# main.net
KiCad netlist of a schematic drawn in EAGLE
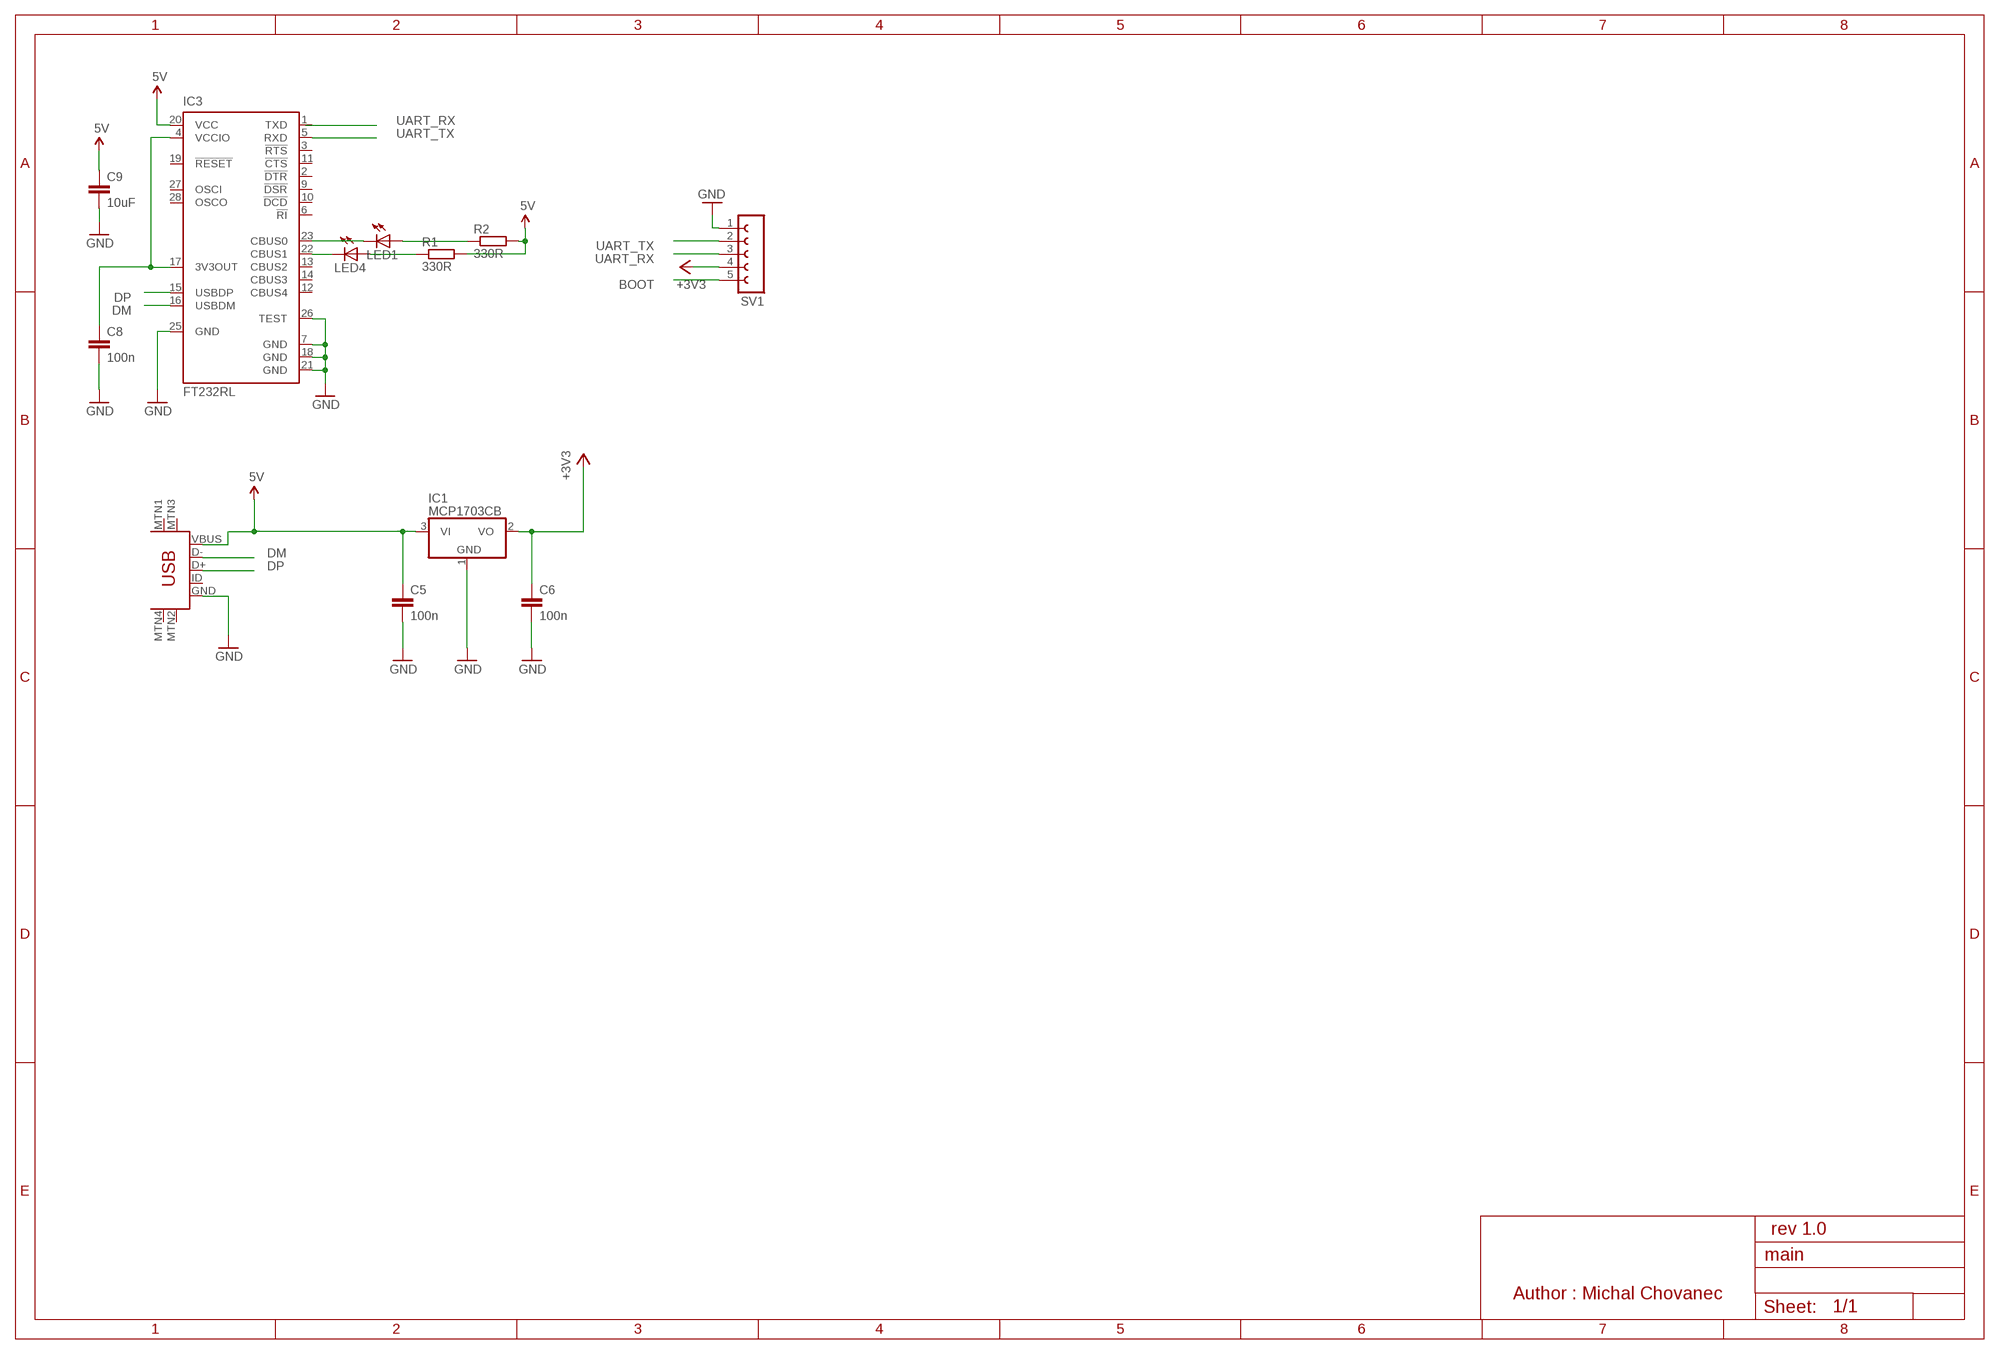
[diagram p0: schematic, sheet 1]

(export (version "E")
  (design (tool "Eeschema 10.0.6"))
  (components
    (comp (ref "C5")
      (value "100n")
      (footprint "eagle-import:C0805")
      (libsource (lib "eagle-import") (part "C-EUC0805"))
    )
    (comp (ref "C6")
      (value "100n")
      (footprint "eagle-import:C0805")
      (libsource (lib "eagle-import") (part "C-EUC0805"))
    )
    (comp (ref "C8")
      (value "100n")
      (footprint "eagle-import:C0805")
      (libsource (lib "eagle-import") (part "C-EUC0805"))
    )
    (comp (ref "C9")
      (value "10uF")
      (footprint "eagle-import:C0805")
      (libsource (lib "eagle-import") (part "C-EUC0805"))
    )
    (comp (ref "IC1")
      (value "MCP1703CB")
      (footprint "eagle-import:SOT23")
      (libsource (lib "eagle-import") (part "MCP1703CB"))
    )
    (comp (ref "IC3")
      (value "FT232RL")
      (footprint "eagle-import:SSOP28")
      (libsource (lib "eagle-import") (part "FT232RL"))
    )
    (comp (ref "LED1")
      (value "LEDCHIPLED_1206")
      (footprint "eagle-import:CHIPLED_1206")
      (libsource (lib "eagle-import") (part "LEDCHIPLED_1206"))
    )
    (comp (ref "LED4")
      (value "LEDCHIPLED_1206")
      (footprint "eagle-import:CHIPLED_1206")
      (libsource (lib "eagle-import") (part "LEDCHIPLED_1206"))
    )
    (comp (ref "R1")
      (value "330R")
      (footprint "eagle-import:M0805")
      (libsource (lib "eagle-import") (part "R-EU_M0805"))
    )
    (comp (ref "R2")
      (value "330R")
      (footprint "eagle-import:M0805")
      (libsource (lib "eagle-import") (part "R-EU_M0805"))
    )
    (comp (ref "SV1")
      (value "FE05-1")
      (footprint "eagle-import:FE05-1")
      (libsource (lib "eagle-import") (part "FE05-1"))
    )
    (comp (ref "U$1")
      (value "USB-MINIB-5PIN")
      (footprint "eagle-import:USB-MINIB")
      (libsource (lib "eagle-import") (part "USB-MINIB-5PIN"))
    )
  )
  (nets
    (net (code "1") (name "+3V3") (class "Default")
      (node (ref "C6") (pin "1") (pinfunction "1_1") (pintype "passive"))
      (node (ref "IC1") (pin "2") (pinfunction "VO_2") (pintype "passive"))
      (node (ref "SV1") (pin "4") (pinfunction "4_4") (pintype "passive"))
    )
    (net (code "2") (name "/BOOT") (class "Default")
      (node (ref "SV1") (pin "5") (pinfunction "5_5") (pintype "passive"))
    )
    (net (code "3") (name "/DM") (class "Default")
      (node (ref "IC3") (pin "16") (pinfunction "USBDM_16") (pintype "bidirectional"))
      (node (ref "U$1") (pin "D-") (pinfunction "D-_D-") (pintype "bidirectional"))
    )
    (net (code "4") (name "/DP") (class "Default")
      (node (ref "IC3") (pin "15") (pinfunction "USBDP_15") (pintype "bidirectional"))
      (node (ref "U$1") (pin "D+") (pinfunction "D+_D+") (pintype "bidirectional"))
    )
    (net (code "5") (name "/UART_RX") (class "Default")
      (node (ref "SV1") (pin "3") (pinfunction "3_3") (pintype "passive"))
    )
    (net (code "6") (name "/UART_TX") (class "Default")
      (node (ref "IC3") (pin "5") (pinfunction "RXD_5") (pintype "input"))
      (node (ref "SV1") (pin "2") (pinfunction "2_2") (pintype "passive"))
    )
    (net (code "7") (name "5V") (class "Default")
      (node (ref "C5") (pin "1") (pinfunction "1_1") (pintype "passive"))
      (node (ref "C9") (pin "1") (pinfunction "1_1") (pintype "passive"))
      (node (ref "IC1") (pin "3") (pinfunction "VI_3") (pintype "input"))
      (node (ref "IC3") (pin "20") (pinfunction "VCC_20") (pintype "power_in"))
      (node (ref "R1") (pin "2") (pinfunction "2_2") (pintype "passive"))
      (node (ref "R2") (pin "2") (pinfunction "2_2") (pintype "passive"))
      (node (ref "U$1") (pin "VBUS") (pinfunction "VBUS_VBUS") (pintype "bidirectional"))
    )
    (net (code "8") (name "GND") (class "Default")
      (node (ref "C5") (pin "2") (pinfunction "2_2") (pintype "passive"))
      (node (ref "C6") (pin "2") (pinfunction "2_2") (pintype "passive"))
      (node (ref "C8") (pin "2") (pinfunction "2_2") (pintype "passive"))
      (node (ref "C9") (pin "2") (pinfunction "2_2") (pintype "passive"))
      (node (ref "IC1") (pin "1") (pinfunction "GND_1") (pintype "passive"))
      (node (ref "IC3") (pin "18") (pinfunction "GND_18") (pintype "power_in"))
      (node (ref "IC3") (pin "21") (pinfunction "GND_21") (pintype "power_in"))
      (node (ref "IC3") (pin "25") (pinfunction "GND_25") (pintype "power_in"))
      (node (ref "IC3") (pin "26") (pinfunction "TEST_26") (pintype "input"))
      (node (ref "IC3") (pin "7") (pinfunction "GND_7") (pintype "power_in"))
      (node (ref "SV1") (pin "1") (pinfunction "1_1") (pintype "passive"))
      (node (ref "U$1") (pin "GND") (pinfunction "GND_GND") (pintype "bidirectional"))
    )
    (net (code "9") (name "Net-(IC3-3V3OUT)") (class "Default")
      (node (ref "C8") (pin "1") (pinfunction "1_1") (pintype "passive"))
      (node (ref "IC3") (pin "17") (pinfunction "3V3OUT_17") (pintype "output"))
      (node (ref "IC3") (pin "4") (pinfunction "VCCIO_4") (pintype "power_in"))
    )
    (net (code "10") (name "Net-(IC3-CBUS0)") (class "Default")
      (node (ref "IC3") (pin "23") (pinfunction "CBUS0_23") (pintype "bidirectional"))
      (node (ref "LED1") (pin "C") (pinfunction "C_C") (pintype "passive"))
    )
    (net (code "11") (name "Net-(IC3-CBUS1)") (class "Default")
      (node (ref "IC3") (pin "22") (pinfunction "CBUS1_22") (pintype "bidirectional"))
      (node (ref "LED4") (pin "C") (pinfunction "C_C") (pintype "passive"))
    )
    (net (code "12") (name "Net-(LED1-PadA)") (class "Default")
      (node (ref "LED1") (pin "A") (pinfunction "A_A") (pintype "passive"))
      (node (ref "R2") (pin "1") (pinfunction "1_1") (pintype "passive"))
    )
    (net (code "13") (name "Net-(LED4-PadA)") (class "Default")
      (node (ref "LED4") (pin "A") (pinfunction "A_A") (pintype "passive"))
      (node (ref "R1") (pin "1") (pinfunction "1_1") (pintype "passive"))
    )
    (net (code "14") (name "unconnected-(IC3-CBUS2-Pad13)") (class "Default")
      (node (ref "IC3") (pin "13") (pinfunction "CBUS2_13") (pintype "bidirectional"))
    )
    (net (code "15") (name "unconnected-(IC3-CBUS3-Pad14)") (class "Default")
      (node (ref "IC3") (pin "14") (pinfunction "CBUS3_14") (pintype "bidirectional"))
    )
    (net (code "16") (name "unconnected-(IC3-CBUS4-Pad12)") (class "Default")
      (node (ref "IC3") (pin "12") (pinfunction "CBUS4_12") (pintype "bidirectional"))
    )
    (net (code "17") (name "unconnected-(IC3-OSCI-Pad27)") (class "Default")
      (node (ref "IC3") (pin "27") (pinfunction "OSCI_27") (pintype "input"))
    )
    (net (code "18") (name "unconnected-(IC3-OSCO-Pad28)") (class "Default")
      (node (ref "IC3") (pin "28") (pinfunction "OSCO_28") (pintype "output"))
    )
    (net (code "19") (name "unconnected-(IC3-TXD-Pad1)") (class "Default")
      (node (ref "IC3") (pin "1") (pinfunction "TXD_1") (pintype "output"))
    )
    (net (code "20") (name "unconnected-(IC3-~{CTS}-Pad11)") (class "Default")
      (node (ref "IC3") (pin "11") (pinfunction "~{CTS}_11") (pintype "input"))
    )
    (net (code "21") (name "unconnected-(IC3-~{DCD}-Pad10)") (class "Default")
      (node (ref "IC3") (pin "10") (pinfunction "~{DCD}_10") (pintype "input"))
    )
    (net (code "22") (name "unconnected-(IC3-~{DSR}-Pad9)") (class "Default")
      (node (ref "IC3") (pin "9") (pinfunction "~{DSR}_9") (pintype "input"))
    )
    (net (code "23") (name "unconnected-(IC3-~{DTR}-Pad2)") (class "Default")
      (node (ref "IC3") (pin "2") (pinfunction "~{DTR}_2") (pintype "output"))
    )
    (net (code "24") (name "unconnected-(IC3-~{RESET}-Pad19)") (class "Default")
      (node (ref "IC3") (pin "19") (pinfunction "~{RESET}_19") (pintype "input"))
    )
    (net (code "25") (name "unconnected-(IC3-~{RI}-Pad6)") (class "Default")
      (node (ref "IC3") (pin "6") (pinfunction "~{RI}_6") (pintype "input"))
    )
    (net (code "26") (name "unconnected-(IC3-~{RTS}-Pad3)") (class "Default")
      (node (ref "IC3") (pin "3") (pinfunction "~{RTS}_3") (pintype "output"))
    )
    (net (code "27") (name "unconnected-(U$1-MTN1-PadMTN3)") (class "Default")
      (node (ref "U$1") (pin "MTN3") (pinfunction "MTN1_MTN3") (pintype "bidirectional"))
    )
    (net (code "28") (name "unconnected-(U$1-MTN2-PadMTN1)") (class "Default")
      (node (ref "U$1") (pin "MTN1") (pinfunction "MTN2_MTN1") (pintype "bidirectional"))
    )
    (net (code "29") (name "unconnected-(U$1-MTN3-PadMTN2)") (class "Default")
      (node (ref "U$1") (pin "MTN2") (pinfunction "MTN3_MTN2") (pintype "bidirectional"))
    )
    (net (code "30") (name "unconnected-(U$1-PadID)") (class "Default")
      (node (ref "U$1") (pin "ID") (pinfunction "ID_ID") (pintype "bidirectional"))
    )
    (net (code "31") (name "unconnected-(U$1-PadMTN4)") (class "Default")
      (node (ref "U$1") (pin "MTN4") (pinfunction "MTN4_MTN4") (pintype "bidirectional"))
    )
  )
)
